# NG6011_IR_Dot_Projector.net
KiCad netlist of a schematic drawn in Altium Designer
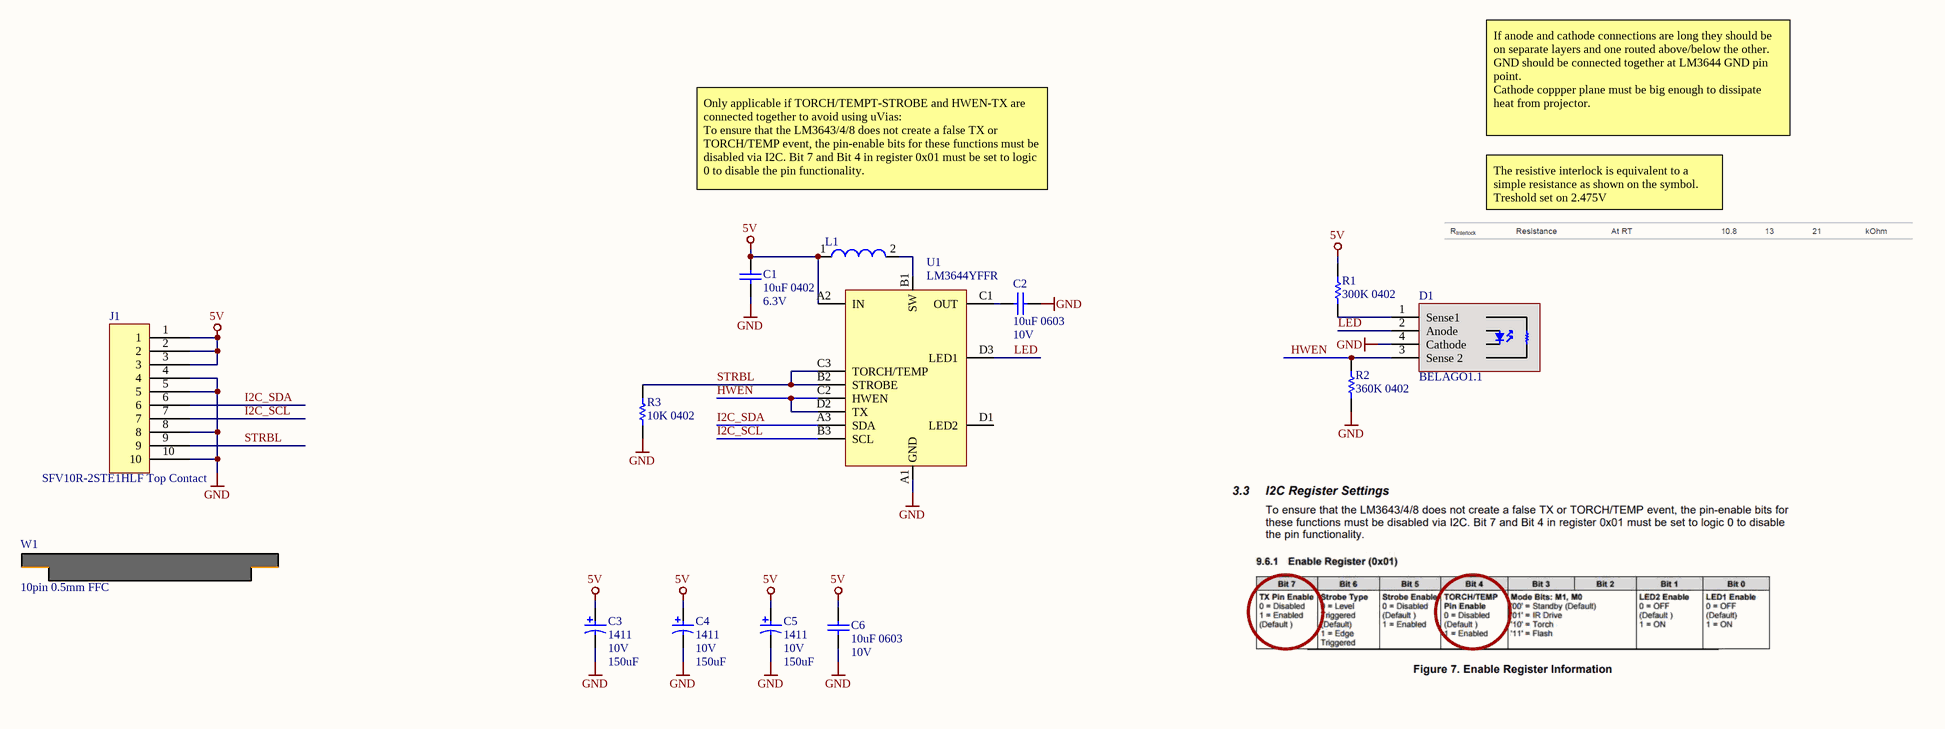
[diagram p0: NG6011_IR_Dot_Projector.SchDoc]

(export (version "E")
  (design (tool "Eeschema 10.0.6"))
  (components
    (comp (ref "C1")
      (value "10uF 0402")
      (footprint "CAP_Altium_Vault_Generic:CAPC0402(1005)70_L")
      (description "CAP CER 10UF 6.3V X5R 0402 20%")
      (fields (field (name "TOLERANCE") "20%") (field (name "VOLTAGE RATING") "6.3V"))
      (libsource (lib "LuxonisMaster") (part "GRM155R60J106ME15D"))
    )
    (comp (ref "C2")
      (value "10uF 0603")
      (footprint "CAP_Altium_Vault_Generic:CAPC0603(1608)100_L")
      (description "CAP CER 10UF 10V X5R 0603 20%")
      (fields (field (name "TOLERANCE") "20%") (field (name "VOLTAGE RATING") "10V"))
      (libsource (lib "LuxonisMaster") (part "GRM188R61A106ME69D"))
    )
    (comp (ref "C3")
      (value "150uF 1206 10V tantal")
      (footprint "RESTL1210(3225)_N")
      (fields
        (field (name "SIZE CODE") "1411")
        (field (name "RATED DC VOLTAGE (URDC)") "10V")
        (field (name "CAPACITANCE") "150uF")
      )
      (libsource (lib "NG6011") (part "TLJB157M010R0500"))
    )
    (comp (ref "C4")
      (value "150uF 1206 10V tantal")
      (footprint "RESTL1210(3225)_N")
      (fields
        (field (name "SIZE CODE") "1411")
        (field (name "RATED DC VOLTAGE (URDC)") "10V")
        (field (name "CAPACITANCE") "150uF")
      )
      (libsource (lib "NG6011") (part "TLJB157M010R0500"))
    )
    (comp (ref "C5")
      (value "150uF 1206 10V tantal")
      (footprint "RESTL1210(3225)_N")
      (fields
        (field (name "SIZE CODE") "1411")
        (field (name "RATED DC VOLTAGE (URDC)") "10V")
        (field (name "CAPACITANCE") "150uF")
      )
      (libsource (lib "NG6011") (part "TLJB157M010R0500"))
    )
    (comp (ref "C6")
      (value "10uF 0603")
      (footprint "CAP_Altium_Vault_Generic:CAPC0603(1608)100_L")
      (description "CAP CER 10UF 10V X5R 0603 20%")
      (fields (field (name "TOLERANCE") "20%") (field (name "VOLTAGE RATING") "10V"))
      (libsource (lib "LuxonisMaster") (part "GRM188R61A106ME69D"))
    )
    (comp (ref "D1")
      (value "BELAGO1.1")
      (footprint "Belago1.1")
      (description "Dot-Pattern Infrared Illuminator for 3D Stereoscopic\r\nImaging AQAA-20")
      (libsource (lib "NG6011") (part "BELAGO1.1"))
    )
    (comp (ref "J1")
      (value "SFV10R-2STE1HLF Top Contact")
      (footprint "SFV10R-2STE1HLF")
      (description "CONN FFC TOP 10POS 0.50MM R/A")
      (libsource (lib "LuxonisMaster") (part "SFV10R-2STE1HLF"))
    )
    (comp (ref "L1")
      (value "1uH, 3.2A, 20%")
      (footprint "LuxonisMaster:DFE252012P-1R0M=P2")
      (description "FIXED IND 1UH 3.2A 42 MOHM SMD")
      (fields
        (field (name "MANUFACTURER") "Murata")
        (field (name "MANUFACTURER PART NUMBER") "DFE252012P-1R0M=P2")
      )
      (libsource (lib "LuxonisMaster") (part "DFE252012P-1R0M=P2"))
    )
    (comp (ref "R1")
      (value "300K 0402")
      (footprint "RES_Altium_Vault_Generic:RESC0402(1005)_L")
      (description "RES SMD 300K OHM 1% 1/16W 0402")
      (fields (field (name "TOLERANCE") "1%"))
      (libsource (lib "LuxonisMaster") (part "RC0402FR-07300KL"))
    )
    (comp (ref "R2")
      (value "360K 0402")
      (footprint "RES_Altium_Vault_Generic:RESC0402(1005)_L")
      (fields (field (name "TOLERANCE") "1%"))
      (libsource (lib "LuxonisMaster") (part "RC0402FR-07360KL"))
    )
    (comp (ref "R3")
      (value "10K 0402")
      (footprint "RES_Altium_Vault_Generic:RESC0402(1005)_L")
      (fields (field (name "TOLERANCE") "1%"))
      (libsource (lib "LuxonisMaster") (part "RC0402FR-1310KL"))
    )
    (comp (ref "U1")
      (value "LM3644YFFR")
      (footprint "LM3644YFFR")
      (description "LED Driver, 2-Segment, PBGA12")
      (libsource (lib "NG6011") (part "LM3644"))
    )
    (comp (ref "W1")
      (value "10pin 0.5mm FFC")
      (description "FFC Jumper Cable 10Conductors 0.152m 60VAC 0.5A Bag")
      (libsource (lib "NG6011") (part "0152660105"))
    )
  )
  (nets
    (net (code "1") (name "/HWEN") (class "Default")
      (node (ref "D1") (pin "3") (pinfunction "Sense_2_3") (pintype "passive"))
      (node (ref "R2") (pin "2") (pinfunction "2_2") (pintype "passive"))
      (node (ref "U1") (pin "C2") (pinfunction "HWEN_C2") (pintype "passive"))
      (node (ref "U1") (pin "D2") (pinfunction "TX_D2") (pintype "passive"))
    )
    (net (code "2") (name "/I2C_SCL") (class "Default")
      (node (ref "J1") (pin "7") (pinfunction "7_7") (pintype "passive"))
      (node (ref "U1") (pin "B3") (pinfunction "SCL_B3") (pintype "passive"))
    )
    (net (code "3") (name "/I2C_SDA") (class "Default")
      (node (ref "J1") (pin "6") (pinfunction "6_6") (pintype "passive"))
      (node (ref "U1") (pin "A3") (pinfunction "SDA_A3") (pintype "passive"))
    )
    (net (code "4") (name "/LED") (class "Default")
      (node (ref "D1") (pin "2") (pinfunction "Anode_2") (pintype "passive"))
      (node (ref "U1") (pin "D3") (pinfunction "LED1_D3") (pintype "passive"))
    )
    (net (code "5") (name "/STRBL") (class "Default")
      (node (ref "J1") (pin "9") (pinfunction "9_9") (pintype "passive"))
      (node (ref "R3") (pin "2") (pinfunction "2_2") (pintype "passive"))
      (node (ref "U1") (pin "B2") (pinfunction "STROBE_B2") (pintype "passive"))
      (node (ref "U1") (pin "C3") (pinfunction "TORCH/TEMP_C3") (pintype "passive"))
    )
    (net (code "6") (name "5V") (class "Default")
      (node (ref "C1") (pin "2") (pinfunction "2_2") (pintype "passive"))
      (node (ref "C3") (pin "1") (pinfunction "1_1") (pintype "passive"))
      (node (ref "C4") (pin "1") (pinfunction "1_1") (pintype "passive"))
      (node (ref "C5") (pin "1") (pinfunction "1_1") (pintype "passive"))
      (node (ref "C6") (pin "2") (pinfunction "2_2") (pintype "passive"))
      (node (ref "J1") (pin "1") (pinfunction "1_1") (pintype "passive"))
      (node (ref "J1") (pin "2") (pinfunction "2_2") (pintype "passive"))
      (node (ref "J1") (pin "3") (pinfunction "3_3") (pintype "passive"))
      (node (ref "L1") (pin "1") (pinfunction "1_1") (pintype "passive"))
      (node (ref "R1") (pin "2") (pinfunction "2_2") (pintype "passive"))
      (node (ref "U1") (pin "A2") (pinfunction "IN_A2") (pintype "passive"))
    )
    (net (code "7") (name "GND") (class "Default")
      (node (ref "C1") (pin "1") (pinfunction "1_1") (pintype "passive"))
      (node (ref "C2") (pin "2") (pinfunction "2_2") (pintype "passive"))
      (node (ref "C3") (pin "2") (pinfunction "2_2") (pintype "passive"))
      (node (ref "C4") (pin "2") (pinfunction "2_2") (pintype "passive"))
      (node (ref "C5") (pin "2") (pinfunction "2_2") (pintype "passive"))
      (node (ref "C6") (pin "1") (pinfunction "1_1") (pintype "passive"))
      (node (ref "D1") (pin "4") (pinfunction "Cathode_4") (pintype "passive"))
      (node (ref "J1") (pin "10") (pinfunction "10_10") (pintype "passive"))
      (node (ref "J1") (pin "4") (pinfunction "4_4") (pintype "passive"))
      (node (ref "J1") (pin "5") (pinfunction "5_5") (pintype "passive"))
      (node (ref "J1") (pin "8") (pinfunction "8_8") (pintype "passive"))
      (node (ref "R2") (pin "1") (pinfunction "1_1") (pintype "passive"))
      (node (ref "R3") (pin "1") (pinfunction "1_1") (pintype "passive"))
      (node (ref "U1") (pin "A1") (pinfunction "GND_A1") (pintype "passive"))
    )
    (net (code "8") (name "Net-(D1-Sense1)") (class "Default")
      (node (ref "D1") (pin "1") (pinfunction "Sense1_1") (pintype "passive"))
      (node (ref "R1") (pin "1") (pinfunction "1_1") (pintype "passive"))
    )
    (net (code "9") (name "Net-(U1-OUT)") (class "Default")
      (node (ref "C2") (pin "1") (pinfunction "1_1") (pintype "passive"))
      (node (ref "U1") (pin "C1") (pinfunction "OUT_C1") (pintype "passive"))
    )
    (net (code "10") (name "Net-(U1-SW)") (class "Default")
      (node (ref "L1") (pin "2") (pinfunction "2_2") (pintype "passive"))
      (node (ref "U1") (pin "B1") (pinfunction "SW_B1") (pintype "passive"))
    )
    (net (code "11") (name "unconnected-(U1-LED2-PadD1)") (class "Default")
      (node (ref "U1") (pin "D1") (pinfunction "LED2_D1") (pintype "passive"))
    )
  )
)
